# SCHEM_AF.net
KiCad netlist of a schematic drawn in EAGLE
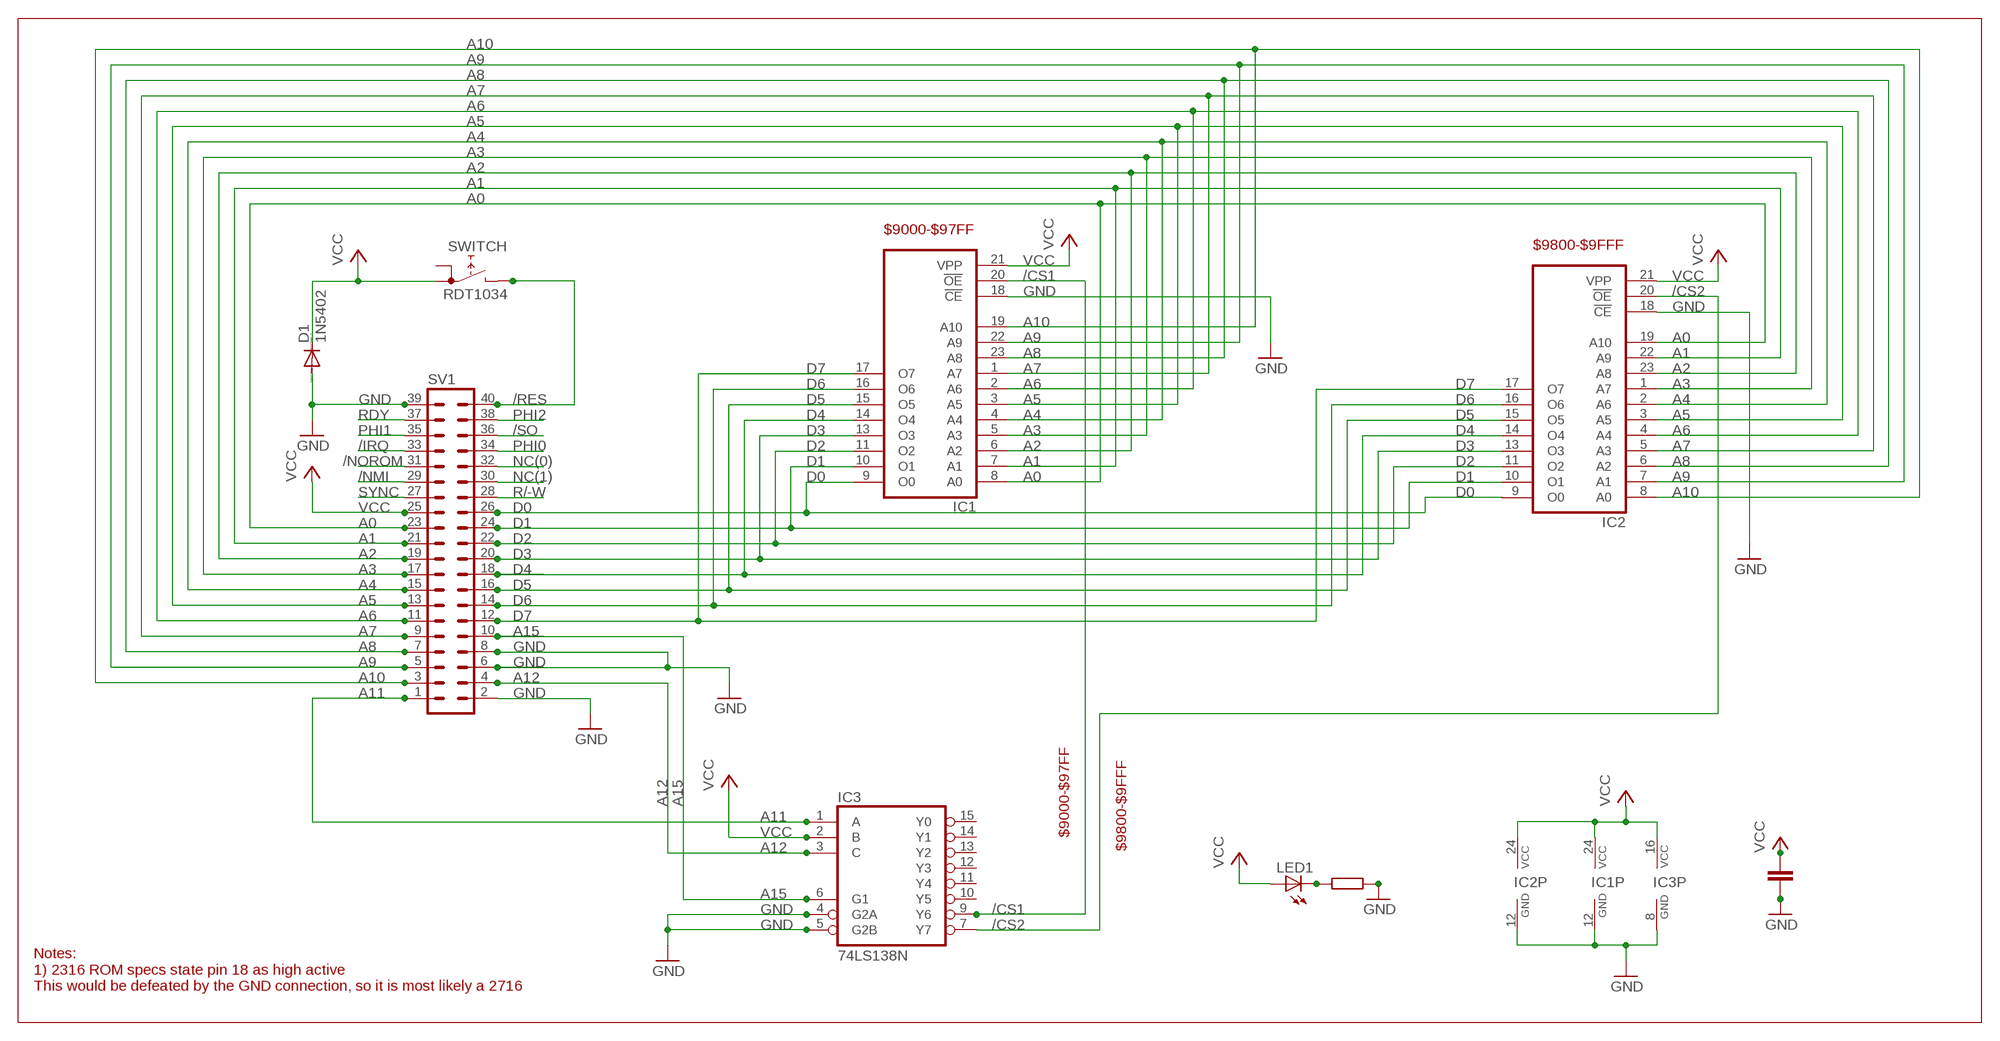
[diagram p0: schematic, sheet 1]

(export (version "E")
  (design (tool "Eeschema 10.0.6"))
  (components
    (comp (ref "D1")
      (value "1N5402")
      (footprint "eagle-import:DO201-15")
      (libsource (lib "eagle-import") (part "1N5400"))
    )
    (comp (ref "IC1")
      (value "2716")
      (footprint "eagle-import:DIL24")
      (libsource (lib "eagle-import") (part "2716"))
    )
    (comp (ref "IC2")
      (value "2716")
      (footprint "eagle-import:DIL24")
      (libsource (lib "eagle-import") (part "2716"))
    )
    (comp (ref "IC3")
      (value "74LS138N")
      (footprint "eagle-import:DIL16")
      (libsource (lib "eagle-import") (part "74138NLS"))
    )
    (comp (ref "LED1")
      (value "LED5MM")
      (footprint "eagle-import:LED5MM")
      (libsource (lib "eagle-import") (part "LED5MM"))
    )
    (comp (ref "SV1")
      (value "40P")
      (footprint "eagle-import:40P")
      (libsource (lib "eagle-import") (part "40P"))
    )
    (comp (ref "SWITCH")
      (value "RDT1034")
      (footprint "eagle-import:RDT1034")
      (libsource (lib "eagle-import") (part "RDT1034"))
    )
  )
  (nets
    (net (code "1") (name "/A0") (class "Default")
      (node (ref "IC1") (pin "8") (pinfunction "A0_8") (pintype "input"))
      (node (ref "IC2") (pin "19") (pinfunction "A10_19") (pintype "input"))
      (node (ref "SV1") (pin "23") (pinfunction "23_23") (pintype "passive"))
    )
    (net (code "2") (name "/A1") (class "Default")
      (node (ref "IC1") (pin "7") (pinfunction "A1_7") (pintype "input"))
      (node (ref "IC2") (pin "22") (pinfunction "A9_22") (pintype "input"))
      (node (ref "SV1") (pin "21") (pinfunction "21_21") (pintype "passive"))
    )
    (net (code "3") (name "/A2") (class "Default")
      (node (ref "IC1") (pin "6") (pinfunction "A2_6") (pintype "input"))
      (node (ref "IC2") (pin "23") (pinfunction "A8_23") (pintype "input"))
      (node (ref "SV1") (pin "19") (pinfunction "19_19") (pintype "passive"))
    )
    (net (code "4") (name "/A3") (class "Default")
      (node (ref "IC1") (pin "5") (pinfunction "A3_5") (pintype "input"))
      (node (ref "IC2") (pin "1") (pinfunction "A7_1") (pintype "input"))
      (node (ref "SV1") (pin "17") (pinfunction "17_17") (pintype "passive"))
    )
    (net (code "5") (name "/A4") (class "Default")
      (node (ref "IC1") (pin "4") (pinfunction "A4_4") (pintype "input"))
      (node (ref "IC2") (pin "2") (pinfunction "A6_2") (pintype "input"))
      (node (ref "SV1") (pin "15") (pinfunction "15_15") (pintype "passive"))
    )
    (net (code "6") (name "/A5") (class "Default")
      (node (ref "IC1") (pin "3") (pinfunction "A5_3") (pintype "input"))
      (node (ref "IC2") (pin "3") (pinfunction "A5_3") (pintype "input"))
      (node (ref "SV1") (pin "13") (pinfunction "13_13") (pintype "passive"))
    )
    (net (code "7") (name "/A6") (class "Default")
      (node (ref "IC1") (pin "2") (pinfunction "A6_2") (pintype "input"))
      (node (ref "IC2") (pin "4") (pinfunction "A4_4") (pintype "input"))
      (node (ref "SV1") (pin "11") (pinfunction "11_11") (pintype "passive"))
    )
    (net (code "8") (name "/A7") (class "Default")
      (node (ref "IC1") (pin "1") (pinfunction "A7_1") (pintype "input"))
      (node (ref "IC2") (pin "5") (pinfunction "A3_5") (pintype "input"))
      (node (ref "SV1") (pin "9") (pinfunction "9_9") (pintype "passive"))
    )
    (net (code "9") (name "/A8") (class "Default")
      (node (ref "IC1") (pin "23") (pinfunction "A8_23") (pintype "input"))
      (node (ref "IC2") (pin "6") (pinfunction "A2_6") (pintype "input"))
      (node (ref "SV1") (pin "7") (pinfunction "7_7") (pintype "passive"))
    )
    (net (code "10") (name "/A9") (class "Default")
      (node (ref "IC1") (pin "22") (pinfunction "A9_22") (pintype "input"))
      (node (ref "IC2") (pin "7") (pinfunction "A1_7") (pintype "input"))
      (node (ref "SV1") (pin "5") (pinfunction "5_5") (pintype "passive"))
    )
    (net (code "11") (name "/A10") (class "Default")
      (node (ref "IC1") (pin "19") (pinfunction "A10_19") (pintype "input"))
      (node (ref "IC2") (pin "8") (pinfunction "A0_8") (pintype "input"))
      (node (ref "SV1") (pin "3") (pinfunction "3_3") (pintype "passive"))
    )
    (net (code "12") (name "/A11") (class "Default")
      (node (ref "IC3") (pin "1") (pinfunction "A_1") (pintype "input"))
      (node (ref "SV1") (pin "1") (pinfunction "1_1") (pintype "passive"))
    )
    (net (code "13") (name "/A12") (class "Default")
      (node (ref "IC3") (pin "3") (pinfunction "C_3") (pintype "input"))
      (node (ref "SV1") (pin "4") (pinfunction "4_4") (pintype "passive"))
    )
    (net (code "14") (name "/A15") (class "Default")
      (node (ref "IC3") (pin "6") (pinfunction "G1_6") (pintype "input"))
      (node (ref "SV1") (pin "10") (pinfunction "10_10") (pintype "passive"))
    )
    (net (code "15") (name "/D0") (class "Default")
      (node (ref "IC1") (pin "9") (pinfunction "O0_9") (pintype "tri_state"))
      (node (ref "IC2") (pin "9") (pinfunction "O0_9") (pintype "tri_state"))
      (node (ref "SV1") (pin "26") (pinfunction "26_26") (pintype "passive"))
    )
    (net (code "16") (name "/D1") (class "Default")
      (node (ref "IC1") (pin "10") (pinfunction "O1_10") (pintype "tri_state"))
      (node (ref "IC2") (pin "10") (pinfunction "O1_10") (pintype "tri_state"))
      (node (ref "SV1") (pin "24") (pinfunction "24_24") (pintype "passive"))
    )
    (net (code "17") (name "/D2") (class "Default")
      (node (ref "IC1") (pin "11") (pinfunction "O2_11") (pintype "tri_state"))
      (node (ref "IC2") (pin "11") (pinfunction "O2_11") (pintype "tri_state"))
      (node (ref "SV1") (pin "22") (pinfunction "22_22") (pintype "passive"))
    )
    (net (code "18") (name "/D3") (class "Default")
      (node (ref "IC1") (pin "13") (pinfunction "O3_13") (pintype "tri_state"))
      (node (ref "IC2") (pin "13") (pinfunction "O3_13") (pintype "tri_state"))
      (node (ref "SV1") (pin "20") (pinfunction "20_20") (pintype "passive"))
    )
    (net (code "19") (name "/D4") (class "Default")
      (node (ref "IC1") (pin "14") (pinfunction "O4_14") (pintype "tri_state"))
      (node (ref "IC2") (pin "14") (pinfunction "O4_14") (pintype "tri_state"))
      (node (ref "SV1") (pin "18") (pinfunction "18_18") (pintype "passive"))
    )
    (net (code "20") (name "/D5") (class "Default")
      (node (ref "IC1") (pin "15") (pinfunction "O5_15") (pintype "tri_state"))
      (node (ref "IC2") (pin "15") (pinfunction "O5_15") (pintype "tri_state"))
      (node (ref "SV1") (pin "16") (pinfunction "16_16") (pintype "passive"))
    )
    (net (code "21") (name "/D6") (class "Default")
      (node (ref "IC1") (pin "16") (pinfunction "O6_16") (pintype "tri_state"))
      (node (ref "IC2") (pin "16") (pinfunction "O6_16") (pintype "tri_state"))
      (node (ref "SV1") (pin "14") (pinfunction "14_14") (pintype "passive"))
    )
    (net (code "22") (name "/D7") (class "Default")
      (node (ref "IC1") (pin "17") (pinfunction "O7_17") (pintype "tri_state"))
      (node (ref "IC2") (pin "17") (pinfunction "O7_17") (pintype "tri_state"))
      (node (ref "SV1") (pin "12") (pinfunction "12_12") (pintype "passive"))
    )
    (net (code "23") (name "/NC(0)") (class "Default")
      (node (ref "SV1") (pin "32") (pinfunction "32_32") (pintype "passive"))
    )
    (net (code "24") (name "/NC(1)") (class "Default")
      (node (ref "SV1") (pin "30") (pinfunction "30_30") (pintype "passive"))
    )
    (net (code "25") (name "/PHI0") (class "Default")
      (node (ref "SV1") (pin "34") (pinfunction "34_34") (pintype "passive"))
    )
    (net (code "26") (name "/PHI1") (class "Default")
      (node (ref "SV1") (pin "35") (pinfunction "35_35") (pintype "passive"))
    )
    (net (code "27") (name "/PHI2") (class "Default")
      (node (ref "SV1") (pin "38") (pinfunction "38_38") (pintype "passive"))
    )
    (net (code "28") (name "/RDY") (class "Default")
      (node (ref "SV1") (pin "37") (pinfunction "37_37") (pintype "passive"))
    )
    (net (code "29") (name "/R{slash}-W") (class "Default")
      (node (ref "SV1") (pin "28") (pinfunction "28_28") (pintype "passive"))
    )
    (net (code "30") (name "/SYNC") (class "Default")
      (node (ref "SV1") (pin "27") (pinfunction "27_27") (pintype "passive"))
    )
    (net (code "31") (name "/{slash}CS1") (class "Default")
      (node (ref "IC1") (pin "20") (pinfunction "~{OE}_20") (pintype "input"))
      (node (ref "IC3") (pin "9") (pinfunction "Y6_9") (pintype "output"))
    )
    (net (code "32") (name "/{slash}CS2") (class "Default")
      (node (ref "IC2") (pin "20") (pinfunction "~{OE}_20") (pintype "input"))
      (node (ref "IC3") (pin "7") (pinfunction "Y7_7") (pintype "output"))
    )
    (net (code "33") (name "/{slash}IRQ") (class "Default")
      (node (ref "SV1") (pin "33") (pinfunction "33_33") (pintype "passive"))
    )
    (net (code "34") (name "/{slash}NMI") (class "Default")
      (node (ref "SV1") (pin "29") (pinfunction "29_29") (pintype "passive"))
    )
    (net (code "35") (name "/{slash}NOROM") (class "Default")
      (node (ref "SV1") (pin "31") (pinfunction "31_31") (pintype "passive"))
    )
    (net (code "36") (name "/{slash}RES") (class "Default")
      (node (ref "SV1") (pin "40") (pinfunction "40_40") (pintype "passive"))
      (node (ref "SWITCH") (pin "B") (pinfunction "B_B") (pintype "passive"))
    )
    (net (code "37") (name "/{slash}SO") (class "Default")
      (node (ref "SV1") (pin "36") (pinfunction "36_36") (pintype "passive"))
    )
    (net (code "38") (name "GND") (class "Default")
      (node (ref "D1") (pin "A") (pinfunction "A_A") (pintype "passive"))
      (node (ref "IC1") (pin "12") (pinfunction "GND_12") (pintype "power_in"))
      (node (ref "IC1") (pin "18") (pinfunction "~{CE}_18") (pintype "input"))
      (node (ref "IC2") (pin "12") (pinfunction "GND_12") (pintype "power_in"))
      (node (ref "IC2") (pin "18") (pinfunction "~{CE}_18") (pintype "input"))
      (node (ref "IC3") (pin "4") (pinfunction "G2A_4") (pintype "input"))
      (node (ref "IC3") (pin "5") (pinfunction "G2B_5") (pintype "input"))
      (node (ref "IC3") (pin "8") (pinfunction "GND_8") (pintype "power_in"))
      (node (ref "SV1") (pin "2") (pinfunction "2_2") (pintype "passive"))
      (node (ref "SV1") (pin "39") (pinfunction "39_39") (pintype "passive"))
      (node (ref "SV1") (pin "6") (pinfunction "6_6") (pintype "passive"))
      (node (ref "SV1") (pin "8") (pinfunction "8_8") (pintype "passive"))
    )
    (net (code "39") (name "VCC") (class "Default")
      (node (ref "D1") (pin "C") (pinfunction "C_C") (pintype "passive"))
      (node (ref "IC1") (pin "21") (pinfunction "VPP_21") (pintype "input"))
      (node (ref "IC1") (pin "24") (pinfunction "VCC_24") (pintype "power_in"))
      (node (ref "IC2") (pin "21") (pinfunction "VPP_21") (pintype "input"))
      (node (ref "IC2") (pin "24") (pinfunction "VCC_24") (pintype "power_in"))
      (node (ref "IC3") (pin "16") (pinfunction "VCC_16") (pintype "power_in"))
      (node (ref "IC3") (pin "2") (pinfunction "B_2") (pintype "input"))
      (node (ref "LED1") (pin "A") (pinfunction "A_A") (pintype "passive"))
      (node (ref "SV1") (pin "25") (pinfunction "25_25") (pintype "passive"))
      (node (ref "SWITCH") (pin "A1") (pinfunction "A1_A1") (pintype "passive"))
    )
    (net (code "40") (name "unconnected-(IC3A-Y0-Pad15)") (class "Default")
      (node (ref "IC3") (pin "15") (pinfunction "Y0_15") (pintype "output"))
    )
    (net (code "41") (name "unconnected-(IC3A-Y1-Pad14)") (class "Default")
      (node (ref "IC3") (pin "14") (pinfunction "Y1_14") (pintype "output"))
    )
    (net (code "42") (name "unconnected-(IC3A-Y2-Pad13)") (class "Default")
      (node (ref "IC3") (pin "13") (pinfunction "Y2_13") (pintype "output"))
    )
    (net (code "43") (name "unconnected-(IC3A-Y3-Pad12)") (class "Default")
      (node (ref "IC3") (pin "12") (pinfunction "Y3_12") (pintype "output"))
    )
    (net (code "44") (name "unconnected-(IC3A-Y4-Pad11)") (class "Default")
      (node (ref "IC3") (pin "11") (pinfunction "Y4_11") (pintype "output"))
    )
    (net (code "45") (name "unconnected-(IC3A-Y5-Pad10)") (class "Default")
      (node (ref "IC3") (pin "10") (pinfunction "Y5_10") (pintype "output"))
    )
    (net (code "46") (name "unconnected-(LED1-C-PadK)") (class "Default")
      (node (ref "LED1") (pin "K") (pinfunction "C_K") (pintype "passive"))
    )
    (net (code "47") (name "unconnected-(SWITCH-PadA)") (class "Default")
      (node (ref "SWITCH") (pin "A") (pinfunction "A_A") (pintype "passive"))
    )
  )
)
